# DDS_OUT_channel.net
KiCad netlist of a schematic drawn in Altium Designer
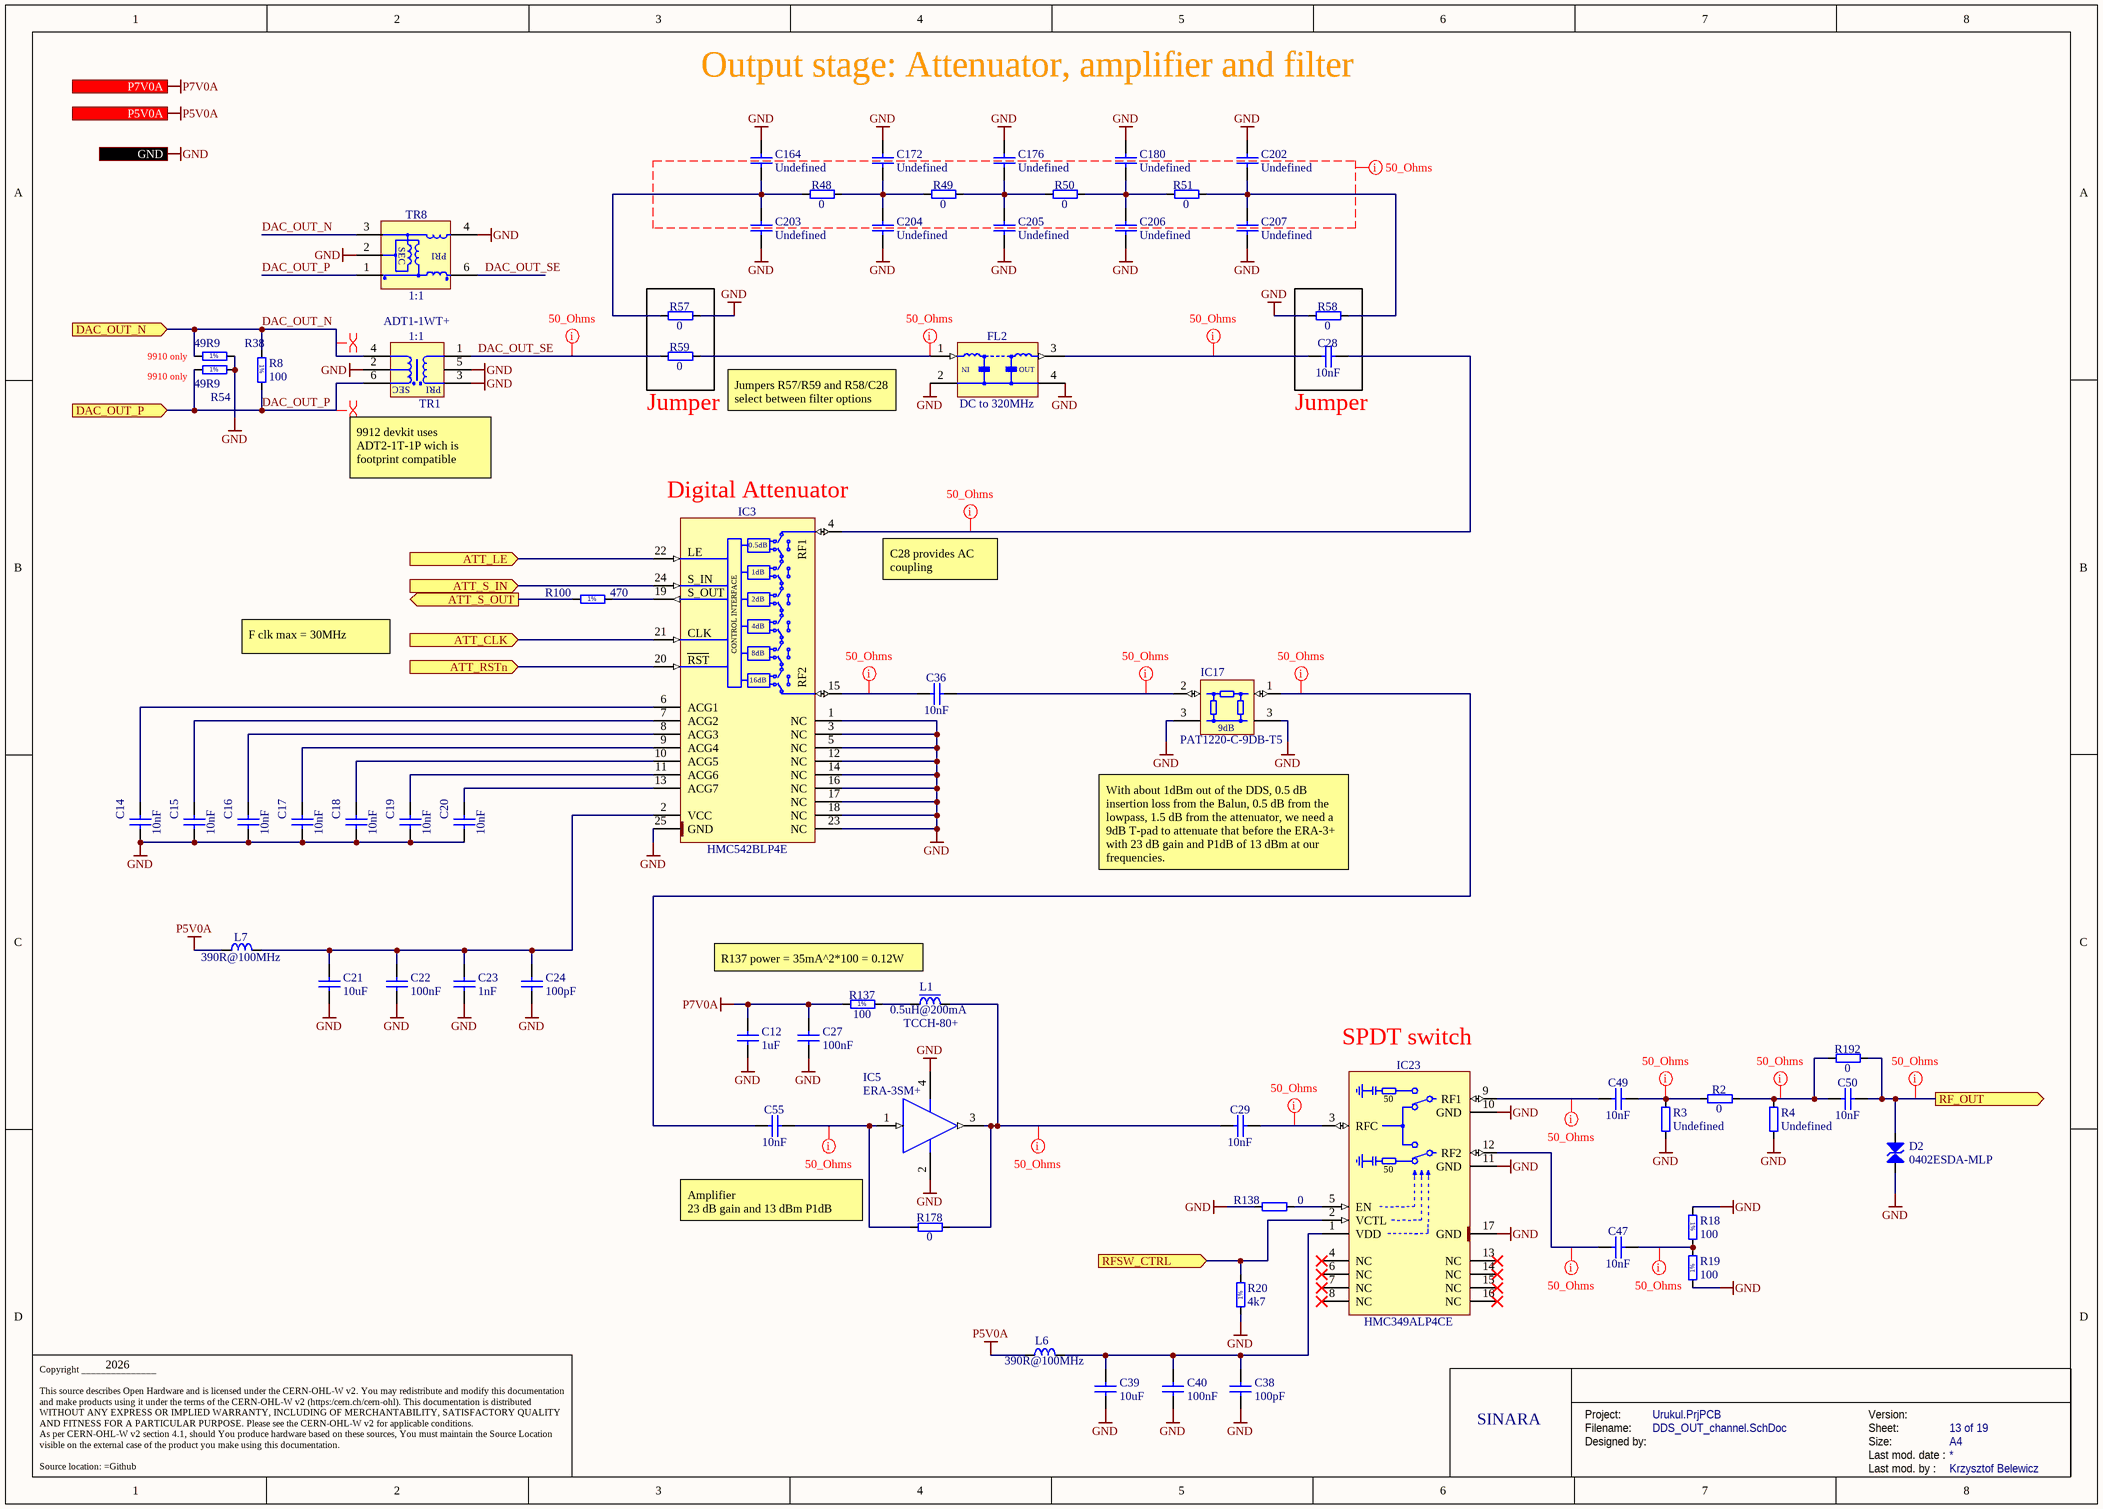
[diagram p0: DDS_OUT_channel.SchDoc]

(export (version "E")
  (design (tool "Eeschema 10.0.6"))
  (components
    (comp (ref "C12")
      (value "1uF")
      (footprint "CAPC2012X140N")
      (description "Non-polarised capacitor")
      (fields
        (field (name "PART NUMBER") "CC0805_1UF_35V_20%_X7R")
        (field (name "VOLTAGE") "35V")
        (field (name "AUTHOR") "CERN DEM JLC")
      )
      (libsource (lib "Capacitors") (part "Capacitor - non polarized"))
    )
    (comp (ref "C14")
      (value "10nF")
      (footprint "CAPC1005X55N")
      (description "Non-polarised capacitor")
      (fields
        (field (name "PART NUMBER") "CC0402_10NF_16V_10%_X7R")
        (field (name "VOLTAGE") "16V")
        (field (name "AUTHOR") "CERN DEM JLC")
      )
      (libsource (lib "Capacitors") (part "Capacitor - non polarized"))
    )
    (comp (ref "C15")
      (value "10nF")
      (footprint "CAPC1005X55N")
      (description "Non-polarised capacitor")
      (fields
        (field (name "PART NUMBER") "CC0402_10NF_16V_10%_X7R")
        (field (name "VOLTAGE") "16V")
        (field (name "AUTHOR") "CERN DEM JLC")
      )
      (libsource (lib "Capacitors") (part "Capacitor - non polarized"))
    )
    (comp (ref "C16")
      (value "10nF")
      (footprint "CAPC1005X55N")
      (description "Non-polarised capacitor")
      (fields
        (field (name "PART NUMBER") "CC0402_10NF_16V_10%_X7R")
        (field (name "VOLTAGE") "16V")
        (field (name "AUTHOR") "CERN DEM JLC")
      )
      (libsource (lib "Capacitors") (part "Capacitor - non polarized"))
    )
    (comp (ref "C17")
      (value "10nF")
      (footprint "CAPC1005X55N")
      (description "Non-polarised capacitor")
      (fields
        (field (name "PART NUMBER") "CC0402_10NF_16V_10%_X7R")
        (field (name "VOLTAGE") "16V")
        (field (name "AUTHOR") "CERN DEM JLC")
      )
      (libsource (lib "Capacitors") (part "Capacitor - non polarized"))
    )
    (comp (ref "C18")
      (value "10nF")
      (footprint "CAPC1005X55N")
      (description "Non-polarised capacitor")
      (fields
        (field (name "PART NUMBER") "CC0402_10NF_16V_10%_X7R")
        (field (name "VOLTAGE") "16V")
        (field (name "AUTHOR") "CERN DEM JLC")
      )
      (libsource (lib "Capacitors") (part "Capacitor - non polarized"))
    )
    (comp (ref "C19")
      (value "10nF")
      (footprint "CAPC1005X55N")
      (description "Non-polarised capacitor")
      (fields
        (field (name "PART NUMBER") "CC0402_10NF_16V_10%_X7R")
        (field (name "VOLTAGE") "16V")
        (field (name "AUTHOR") "CERN DEM JLC")
      )
      (libsource (lib "Capacitors") (part "Capacitor - non polarized"))
    )
    (comp (ref "C20")
      (value "10nF")
      (footprint "CAPC1005X55N")
      (description "Non-polarised capacitor")
      (fields
        (field (name "PART NUMBER") "CC0402_10NF_16V_10%_X7R")
        (field (name "VOLTAGE") "16V")
        (field (name "AUTHOR") "CERN DEM JLC")
      )
      (libsource (lib "Capacitors") (part "Capacitor - non polarized"))
    )
    (comp (ref "C21")
      (value "10uF")
      (footprint "CAPC1608X80N")
      (description "Non-polarised capacitor")
      (fields
        (field (name "PART NUMBER") "CC0603_10UF_16V_20%_X5R")
        (field (name "VOLTAGE") "16V")
        (field (name "AUTHOR") "CERN DEM MR")
      )
      (libsource (lib "Capacitors") (part "Capacitor - non polarized"))
    )
    (comp (ref "C22")
      (value "100nF")
      (footprint "CAPC1005X55N")
      (description "Non-polarised capacitor")
      (fields
        (field (name "PART NUMBER") "CC0402_100NF_16V_10%_X5R")
        (field (name "VOLTAGE") "16V")
        (field (name "AUTHOR") "CERN DEM JLC")
      )
      (libsource (lib "Capacitors") (part "Capacitor - non polarized"))
    )
    (comp (ref "C23")
      (value "1nF")
      (footprint "CAPC1005X55N")
      (description "Non-polarised capacitor")
      (fields
        (field (name "PART NUMBER") "CC0402_1NF_50V_10%_X7R")
        (field (name "VOLTAGE") "50V")
        (field (name "AUTHOR") "CERN DEM JLC")
      )
      (libsource (lib "Capacitors") (part "Capacitor - non polarized"))
    )
    (comp (ref "C24")
      (value "100pF")
      (footprint "CAPC1005X55N")
      (description "Non-polarised capacitor")
      (fields
        (field (name "PART NUMBER") "CC0402_100PF_50V_5%_C0G")
        (field (name "VOLTAGE") "50V")
        (field (name "AUTHOR") "CERN DEM JLC")
      )
      (libsource (lib "Capacitors") (part "Capacitor - non polarized"))
    )
    (comp (ref "C27")
      (value "100nF")
      (footprint "CAPC1005X55N")
      (description "Non-polarised capacitor")
      (fields
        (field (name "PART NUMBER") "CC0402_100NF_16V_10%_X5R")
        (field (name "VOLTAGE") "16V")
        (field (name "AUTHOR") "CERN DEM JLC")
      )
      (libsource (lib "Capacitors") (part "Capacitor - non polarized"))
    )
    (comp (ref "C28")
      (value "10nF")
      (footprint "CAPC1005X55N")
      (description "Non-polarised capacitor")
      (fields
        (field (name "PART NUMBER") "CC0402_10NF_16V_10%_X7R")
        (field (name "VOLTAGE") "16V")
        (field (name "AUTHOR") "CERN DEM JLC")
      )
      (libsource (lib "Capacitors") (part "Capacitor - non polarized"))
    )
    (comp (ref "C29")
      (value "10nF")
      (footprint "CAPC1005X55N")
      (description "Non-polarised capacitor")
      (fields
        (field (name "PART NUMBER") "CC0402_10NF_16V_10%_X7R")
        (field (name "VOLTAGE") "16V")
        (field (name "AUTHOR") "CERN DEM JLC")
      )
      (libsource (lib "Capacitors") (part "Capacitor - non polarized"))
    )
    (comp (ref "C36")
      (value "10nF")
      (footprint "CAPC1005X55N")
      (description "Non-polarised capacitor")
      (fields
        (field (name "PART NUMBER") "CC0402_10NF_16V_10%_X7R")
        (field (name "VOLTAGE") "16V")
        (field (name "AUTHOR") "CERN DEM JLC")
      )
      (libsource (lib "Capacitors") (part "Capacitor - non polarized"))
    )
    (comp (ref "C38")
      (value "100pF")
      (footprint "CAPC1005X55N")
      (description "Non-polarised capacitor")
      (fields
        (field (name "PART NUMBER") "CC0402_100PF_50V_5%_C0G")
        (field (name "VOLTAGE") "50V")
        (field (name "AUTHOR") "CERN DEM JLC")
      )
      (libsource (lib "Capacitors") (part "Capacitor - non polarized"))
    )
    (comp (ref "C39")
      (value "10uF")
      (footprint "CAPC1608X80N")
      (description "Non-polarised capacitor")
      (fields
        (field (name "PART NUMBER") "CC0603_10UF_16V_20%_X5R")
        (field (name "VOLTAGE") "16V")
        (field (name "AUTHOR") "CERN DEM MR")
      )
      (libsource (lib "Capacitors") (part "Capacitor - non polarized"))
    )
    (comp (ref "C40")
      (value "100nF")
      (footprint "CAPC1005X55N")
      (description "Non-polarised capacitor")
      (fields
        (field (name "PART NUMBER") "CC0402_100NF_16V_10%_X5R")
        (field (name "VOLTAGE") "16V")
        (field (name "AUTHOR") "CERN DEM JLC")
      )
      (libsource (lib "Capacitors") (part "Capacitor - non polarized"))
    )
    (comp (ref "C47")
      (value "10nF")
      (footprint "CAPC1005X55N")
      (description "Non-polarised capacitor")
      (fields
        (field (name "PART NUMBER") "CC0402_10NF_16V_10%_X7R")
        (field (name "VOLTAGE") "16V")
        (field (name "AUTHOR") "CERN DEM JLC")
      )
      (libsource (lib "Capacitors") (part "Capacitor - non polarized"))
    )
    (comp (ref "C49")
      (value "10nF")
      (footprint "CAPC1005X55N")
      (description "Non-polarised capacitor")
      (fields
        (field (name "PART NUMBER") "CC0402_10NF_16V_10%_X7R")
        (field (name "VOLTAGE") "16V")
        (field (name "AUTHOR") "CERN DEM JLC")
      )
      (libsource (lib "Capacitors") (part "Capacitor - non polarized"))
    )
    (comp (ref "C50")
      (value "10nF")
      (footprint "CAPC1005X55N")
      (description "Non-polarised capacitor")
      (fields
        (field (name "PART NUMBER") "CC0402_10NF_16V_10%_X7R")
        (field (name "VOLTAGE") "16V")
        (field (name "AUTHOR") "CERN DEM JLC")
      )
      (libsource (lib "Capacitors") (part "Capacitor - non polarized"))
    )
    (comp (ref "C55")
      (value "10nF")
      (footprint "CAPC1005X55N")
      (description "Non-polarised capacitor")
      (fields
        (field (name "PART NUMBER") "CC0402_10NF_16V_10%_X7R")
        (field (name "VOLTAGE") "16V")
        (field (name "AUTHOR") "CERN DEM JLC")
      )
      (libsource (lib "Capacitors") (part "Capacitor - non polarized"))
    )
    (comp (ref "C164")
      (value "Undefined")
      (footprint "CAPC1005X55N")
      (description "Non-polarised capacitor")
      (fields (field (name "PART NUMBER") "CC0402_NO-VALUE") (field (name "AUTHOR") "CERN DEM JLC"))
      (libsource (lib "Capacitors") (part "Capacitor - non polarized"))
    )
    (comp (ref "C172")
      (value "Undefined")
      (footprint "CAPC1005X55N")
      (description "Non-polarised capacitor")
      (fields (field (name "PART NUMBER") "CC0402_NO-VALUE") (field (name "AUTHOR") "CERN DEM JLC"))
      (libsource (lib "Capacitors") (part "Capacitor - non polarized"))
    )
    (comp (ref "C176")
      (value "Undefined")
      (footprint "CAPC1005X55N")
      (description "Non-polarised capacitor")
      (fields (field (name "PART NUMBER") "CC0402_NO-VALUE") (field (name "AUTHOR") "CERN DEM JLC"))
      (libsource (lib "Capacitors") (part "Capacitor - non polarized"))
    )
    (comp (ref "C180")
      (value "Undefined")
      (footprint "CAPC1005X55N")
      (description "Non-polarised capacitor")
      (fields (field (name "PART NUMBER") "CC0402_NO-VALUE") (field (name "AUTHOR") "CERN DEM JLC"))
      (libsource (lib "Capacitors") (part "Capacitor - non polarized"))
    )
    (comp (ref "C202")
      (value "Undefined")
      (footprint "CAPC1005X55N")
      (description "Non-polarised capacitor")
      (fields (field (name "PART NUMBER") "CC0402_NO-VALUE") (field (name "AUTHOR") "CERN DEM JLC"))
      (libsource (lib "Capacitors") (part "Capacitor - non polarized"))
    )
    (comp (ref "C203")
      (value "Undefined")
      (footprint "CAPC1005X55N")
      (description "Non-polarised capacitor")
      (fields (field (name "PART NUMBER") "CC0402_NO-VALUE") (field (name "AUTHOR") "CERN DEM JLC"))
      (libsource (lib "Capacitors") (part "Capacitor - non polarized"))
    )
    (comp (ref "C204")
      (value "Undefined")
      (footprint "CAPC1005X55N")
      (description "Non-polarised capacitor")
      (fields (field (name "PART NUMBER") "CC0402_NO-VALUE") (field (name "AUTHOR") "CERN DEM JLC"))
      (libsource (lib "Capacitors") (part "Capacitor - non polarized"))
    )
    (comp (ref "C205")
      (value "Undefined")
      (footprint "CAPC1005X55N")
      (description "Non-polarised capacitor")
      (fields (field (name "PART NUMBER") "CC0402_NO-VALUE") (field (name "AUTHOR") "CERN DEM JLC"))
      (libsource (lib "Capacitors") (part "Capacitor - non polarized"))
    )
    (comp (ref "C206")
      (value "Undefined")
      (footprint "CAPC1005X55N")
      (description "Non-polarised capacitor")
      (fields (field (name "PART NUMBER") "CC0402_NO-VALUE") (field (name "AUTHOR") "CERN DEM JLC"))
      (libsource (lib "Capacitors") (part "Capacitor - non polarized"))
    )
    (comp (ref "C207")
      (value "Undefined")
      (footprint "CAPC1005X55N")
      (description "Non-polarised capacitor")
      (fields (field (name "PART NUMBER") "CC0402_NO-VALUE") (field (name "AUTHOR") "CERN DEM JLC"))
      (libsource (lib "Capacitors") (part "Capacitor - non polarized"))
    )
    (comp (ref "D2")
      (value "0402ESDA-MLP")
      (footprint "EATON_0402ESDA-MLP")
      (description "Transient Voltage Suppressor Diode (Bi-Directional)")
      (fields
        (field (name "VOLTAGE") "8kV")
        (field (name "MANUFACTURER") "EATON")
        (field (name "AUTHOR") "CERN DEM MR")
      )
      (libsource (lib "ICs And Semiconductors") (part "Diode TVS Bi-Directional"))
    )
    (comp (ref "FL2")
      (value "DC to 320MHz")
      (footprint "FIL_MINI-CIRCUITS_FV1206")
      (description "50 Ohm DC to 320MHz Low Pass Filter")
      (fields
        (field (name "PART NUMBER") "FIL_MINI-CIRCUITS_LFCN-320")
        (field (name "MANUFACTURER") "MINI-CIRCUITS")
        (field (name "AUTHOR") "CERN DEM JLC")
      )
      (libsource (lib "LIBRARY_SCH") (part "FIL_MINI-CIRCUITS_LFCN-320"))
    )
    (comp (ref "IC3")
      (value "HMC542BLP4E")
      (footprint "QFN50P400X400X100-25N-S295")
      (description "0.5dB LSB GaAs MMIC 6-bit Digital Serial Control Attenuator, DC - 4GHz")
      (fields (field (name "MANUFACTURER") "HITTITE MICROWAVE CORP") (field (name "AUTHOR") "CERN DEM JMW"))
      (libsource (lib "ICs And Semiconductors") (part "HMC542BLP4E"))
    )
    (comp (ref "IC5")
      (value "ERA-3SM+")
      (footprint "MINI-CIRCUITS_WW107")
      (description "DC-3GHz Monolithic Amplifier")
      (fields (field (name "MANUFACTURER") "MINI-CIRCUITS") (field (name "AUTHOR") "GK"))
      (libsource (lib "LIBRARY_SCH") (part "RF_ERA-3SM+"))
    )
    (comp (ref "IC17")
      (value "PAT1220-C-9DB-T5")
      (footprint "SUSUMU_PAT1220")
      (description "DC to 10GHz, 100mw, 50 Ohm, 9dB, Precision chip attenuator")
      (fields (field (name "MANUFACTURER") "SUSUMU") (field (name "AUTHOR") "GK"))
      (libsource (lib "LIBRARY_SCH") (part "RF_PAT1220-C-9DB-T5"))
    )
    (comp (ref "IC23")
      (value "HMC349ALP4CE")
      (footprint "QFN65P400X400X100-17N-S255")
      (description "DC-4GHz High Isolation SPDT Non-Reflective Switch")
      (fields (field (name "MANUFACTURER") "ANALOG DEVICES") (field (name "AUTHOR") "CERN DEM JLC"))
      (libsource (lib "ICs And Semiconductors") (part "HMC349ALP4CE"))
    )
    (comp (ref "L1")
      (value "0.5uH@200mA")
      (footprint "IND_MINI-CIRCUITS_GU1604")
      (description "50 Ohms, 50 to 8200 MHz RF Choke")
      (fields
        (field (name "PART NUMBER") "IND_MINI-CIRCUITS_TCCH-80+")
        (field (name "POWER") "200mA")
        (field (name "MANUFACTURER PART NUMBER") "TCCH-80+")
        (field (name "AUTHOR") "CERN DEM JLC")
      )
      (libsource (lib "Inductors & Transformers") (part "IND_MINI-CIRCUITS_TCCH-80+"))
    )
    (comp (ref "L6")
      (value "390R@100MHz")
      (footprint "INDC1608X95N")
      (description "Inductor")
      (fields
        (field (name "PART NUMBER") "IND0603_TDK_MPZ1608R391A")
        (field (name "POWER") "1.2A")
        (field (name "AUTHOR") "CERN DEM JLC")
      )
      (libsource (lib "Inductors & Transformers") (part "Inductor"))
    )
    (comp (ref "L7")
      (value "390R@100MHz")
      (footprint "INDC1608X95N")
      (description "Inductor")
      (fields
        (field (name "PART NUMBER") "IND0603_TDK_MPZ1608R391A")
        (field (name "POWER") "1.2A")
        (field (name "AUTHOR") "CERN DEM JLC")
      )
      (libsource (lib "") (part "Inductor_1"))
    )
    (comp (ref "R2")
      (value "0")
      (footprint "RESC1005X40N")
      (description "Resistor")
      (fields
        (field (name "PART NUMBER") "R0402_0R_JUMPER")
        (field (name "MANUFACTURER") "GENERIC")
        (field (name "AUTHOR") "CERN DEM JLC")
      )
      (libsource (lib "Resistors") (part "Resistor"))
    )
    (comp (ref "R3")
      (value "Undefined")
      (footprint "RESC1005X40N")
      (description "Resistor")
      (fields (field (name "PART NUMBER") "R0402_NO-VALUE") (field (name "AUTHOR") "CERN DEM JLC"))
      (libsource (lib "Resistors") (part "Resistor"))
    )
    (comp (ref "R4")
      (value "Undefined")
      (footprint "RESC1005X40N")
      (description "Resistor")
      (fields (field (name "PART NUMBER") "R0402_NO-VALUE") (field (name "AUTHOR") "CERN DEM JLC"))
      (libsource (lib "Resistors") (part "Resistor"))
    )
    (comp (ref "R8")
      (value "100")
      (footprint "RESC1005X40N")
      (description "Resistor - 1%")
      (fields
        (field (name "PART NUMBER") "R0402_100R_1%_0.0625W_100PPM")
        (field (name "POWER") "0.0625W")
        (field (name "AUTHOR") "CERN DEM JLC")
      )
      (libsource (lib "Resistors") (part "Resistor - 1%"))
    )
    (comp (ref "R18")
      (value "100")
      (footprint "RESC1005X40N")
      (description "Resistor - 1%")
      (fields
        (field (name "PART NUMBER") "R0402_100R_1%_0.0625W_100PPM")
        (field (name "POWER") "0.0625W")
        (field (name "AUTHOR") "CERN DEM JLC")
      )
      (libsource (lib "Resistors") (part "Resistor - 1%"))
    )
    (comp (ref "R19")
      (value "100")
      (footprint "RESC1005X40N")
      (description "Resistor - 1%")
      (fields
        (field (name "PART NUMBER") "R0402_100R_1%_0.0625W_100PPM")
        (field (name "POWER") "0.0625W")
        (field (name "AUTHOR") "CERN DEM JLC")
      )
      (libsource (lib "Resistors") (part "Resistor - 1%"))
    )
    (comp (ref "R20")
      (value "4k7")
      (footprint "RESC1005X40N")
      (description "Resistor - 1%")
      (fields
        (field (name "PART NUMBER") "R0402_4K7_1%_0.0625W_100PPM")
        (field (name "POWER") "0.0625W")
        (field (name "AUTHOR") "CERN DEM JLC")
      )
      (libsource (lib "Resistors") (part "Resistor - 1%"))
    )
    (comp (ref "R38")
      (value "49R9")
      (footprint "RESC1005X40N")
      (description "Resistor - 1%")
      (fields
        (field (name "PART NUMBER") "R0402_49R9_1%_0.0625W_100PPM")
        (field (name "POWER") "0.0625W")
        (field (name "AUTHOR") "CERN DEM JLC")
      )
      (libsource (lib "Resistors") (part "Resistor - 1%"))
    )
    (comp (ref "R48")
      (value "0")
      (footprint "RESC1005X40N")
      (description "Resistor")
      (fields
        (field (name "PART NUMBER") "R0402_0R_JUMPER")
        (field (name "MANUFACTURER") "GENERIC")
        (field (name "AUTHOR") "CERN DEM JLC")
      )
      (libsource (lib "Resistors") (part "Resistor"))
    )
    (comp (ref "R49")
      (value "0")
      (footprint "RESC1005X40N")
      (description "Resistor")
      (fields
        (field (name "PART NUMBER") "R0402_0R_JUMPER")
        (field (name "MANUFACTURER") "GENERIC")
        (field (name "AUTHOR") "CERN DEM JLC")
      )
      (libsource (lib "Resistors") (part "Resistor"))
    )
    (comp (ref "R50")
      (value "0")
      (footprint "RESC1005X40N")
      (description "Resistor")
      (fields
        (field (name "PART NUMBER") "R0402_0R_JUMPER")
        (field (name "MANUFACTURER") "GENERIC")
        (field (name "AUTHOR") "CERN DEM JLC")
      )
      (libsource (lib "Resistors") (part "Resistor"))
    )
    (comp (ref "R51")
      (value "0")
      (footprint "RESC1005X40N")
      (description "Resistor")
      (fields
        (field (name "PART NUMBER") "R0402_0R_JUMPER")
        (field (name "MANUFACTURER") "GENERIC")
        (field (name "AUTHOR") "CERN DEM JLC")
      )
      (libsource (lib "Resistors") (part "Resistor"))
    )
    (comp (ref "R54")
      (value "49R9")
      (footprint "RESC1005X40N")
      (description "Resistor - 1%")
      (fields
        (field (name "PART NUMBER") "R0402_49R9_1%_0.0625W_100PPM")
        (field (name "POWER") "0.0625W")
        (field (name "AUTHOR") "CERN DEM JLC")
      )
      (libsource (lib "Resistors") (part "Resistor - 1%"))
    )
    (comp (ref "R57")
      (value "0")
      (footprint "RESC1005X40N")
      (description "Resistor")
      (fields
        (field (name "PART NUMBER") "R0402_0R_JUMPER")
        (field (name "MANUFACTURER") "GENERIC")
        (field (name "AUTHOR") "CERN DEM JLC")
      )
      (libsource (lib "Resistors") (part "Resistor"))
    )
    (comp (ref "R58")
      (value "0")
      (footprint "RESC1005X40N")
      (description "Resistor")
      (fields
        (field (name "PART NUMBER") "R0402_0R_JUMPER")
        (field (name "MANUFACTURER") "GENERIC")
        (field (name "AUTHOR") "CERN DEM JLC")
      )
      (libsource (lib "Resistors") (part "Resistor"))
    )
    (comp (ref "R59")
      (value "0")
      (footprint "RESC1005X40N")
      (description "Resistor")
      (fields
        (field (name "PART NUMBER") "R0402_0R_JUMPER")
        (field (name "MANUFACTURER") "GENERIC")
        (field (name "AUTHOR") "CERN DEM JLC")
      )
      (libsource (lib "Resistors") (part "Resistor"))
    )
    (comp (ref "R100")
      (value "470")
      (footprint "RESC1005X40N")
      (description "Resistor - 1%")
      (fields
        (field (name "PART NUMBER") "R0402_470R_1%_0.0625W_100PPM")
        (field (name "POWER") "0.0625W")
        (field (name "AUTHOR") "CERN DEM JLC")
      )
      (libsource (lib "Resistors") (part "Resistor - 1%"))
    )
    (comp (ref "R137")
      (value "100")
      (footprint "RESC3216X65N")
      (description "Resistor - 1%")
      (fields
        (field (name "PART NUMBER") "R1206_100R_1%_0.5W_100PPM_VISHAY_CRCW-HP e3")
        (field (name "POWER") "0.5W")
        (field (name "AUTHOR") "CERN DEM JLC")
      )
      (libsource (lib "Resistors") (part "Resistor - 1%"))
    )
    (comp (ref "R138")
      (value "0")
      (footprint "RESC1005X40N")
      (description "Resistor")
      (fields
        (field (name "PART NUMBER") "R0402_0R_JUMPER")
        (field (name "MANUFACTURER") "GENERIC")
        (field (name "AUTHOR") "CERN DEM JLC")
      )
      (libsource (lib "Resistors") (part "Resistor"))
    )
    (comp (ref "R178")
      (value "0")
      (footprint "RESC1608X55N")
      (description "Resistor")
      (fields
        (field (name "PART NUMBER") "R0603_0R_JUMPER")
        (field (name "MANUFACTURER") "GENERIC")
        (field (name "AUTHOR") "CERN DEM JLC")
      )
      (libsource (lib "Resistors") (part "Resistor"))
    )
    (comp (ref "R192")
      (value "0")
      (footprint "RESC1005X40N")
      (description "Resistor")
      (fields
        (field (name "PART NUMBER") "R0402_0R_JUMPER")
        (field (name "MANUFACTURER") "GENERIC")
        (field (name "AUTHOR") "CERN DEM JLC")
      )
      (libsource (lib "Resistors") (part "Resistor"))
    )
    (comp (ref "TR1")
      (value "1:1")
      (footprint "XFMR_MINI-CIRCUITS_CD542")
      (description "75 Ohm 0.4 To 800MHz RF Transformers")
      (fields
        (field (name "PART NUMBER") "XFMR_MINI-CIRCUITS_ADT1-1WT+")
        (field (name "MANUFACTURER") "MINI-CIRCUITS")
        (field (name "MANUFACTURER PART NUMBER") "ADT1-1WT+")
        (field (name "AUTHOR") "CERN DEM JLC")
      )
      (libsource (lib "Inductors & Transformers") (part "XFMR_MINI-CIRCUITS_ADT1-1WT+"))
    )
    (comp (ref "TR8")
      (value "1:1")
      (footprint "XFMR_MINI-CIRCUITS_AT1521")
      (description "50 Ohms 5 To 1500MHz TLT RF Transformer")
      (fields
        (field (name "PART NUMBER") "XFMR_MINI-CIRCUITS_TC1-1T-152X+")
        (field (name "MANUFACTURER") "MINI-CIRCUITS")
        (field (name "AUTHOR") "GK")
      )
      (libsource (lib "Inductors_Transformers") (part "XFMR_MINI-CIRCUITS_TC1-1T-152X+"))
    )
  )
  (nets
    (net (code "1") (name "/ATT_CLK") (class "Default")
      (node (ref "IC3") (pin "21") (pinfunction "SHIFT_CLOCK_21") (pintype "input"))
    )
    (net (code "2") (name "/ATT_LE") (class "Default")
      (node (ref "IC3") (pin "22") (pinfunction "LATCH_ENABLE_22") (pintype "input"))
    )
    (net (code "3") (name "/ATT_RSTn") (class "Default")
      (node (ref "IC3") (pin "20") (pinfunction "~{RESET}_20") (pintype "input"))
    )
    (net (code "4") (name "/ATT_S_IN") (class "Default")
      (node (ref "IC3") (pin "24") (pinfunction "SERIAL_INPUT_24") (pintype "input"))
    )
    (net (code "5") (name "/ATT_S_OUT") (class "Default")
      (node (ref "R100") (pin "1") (pinfunction "1_1") (pintype "passive"))
    )
    (net (code "6") (name "/DAC_OUT_N") (class "Default")
      (node (ref "R38") (pin "1") (pinfunction "1_1") (pintype "passive"))
      (node (ref "R8") (pin "1") (pinfunction "1_1") (pintype "passive"))
      (node (ref "TR1") (pin "4") (pinfunction "S_4") (pintype "passive"))
      (node (ref "TR8") (pin "3") (pinfunction "S_3") (pintype "passive"))
    )
    (net (code "7") (name "/DAC_OUT_P") (class "Default")
      (node (ref "R54") (pin "1") (pinfunction "1_1") (pintype "passive"))
      (node (ref "R8") (pin "2") (pinfunction "2_2") (pintype "passive"))
      (node (ref "TR1") (pin "6") (pinfunction "SDOT_6") (pintype "passive"))
      (node (ref "TR8") (pin "1") (pinfunction "SDOT_1") (pintype "passive"))
    )
    (net (code "8") (name "/DAC_OUT_SE") (class "Default")
      (node (ref "R59") (pin "1") (pinfunction "1_1") (pintype "passive"))
      (node (ref "TR1") (pin "1") (pinfunction "P_1") (pintype "passive"))
      (node (ref "TR8") (pin "6") (pinfunction "PDOT_6") (pintype "passive"))
    )
    (net (code "9") (name "/RFSW_CTRL") (class "Default")
      (node (ref "IC23") (pin "2") (pinfunction "VCTL_2") (pintype "input"))
      (node (ref "R20") (pin "2") (pinfunction "2_2") (pintype "passive"))
    )
    (net (code "10") (name "/RF_OUT") (class "Default")
      (node (ref "C50") (pin "2") (pinfunction "2_2") (pintype "passive"))
      (node (ref "D2") (pin "2") (pinfunction "2_2") (pintype "passive"))
      (node (ref "R192") (pin "2") (pinfunction "2_2") (pintype "passive"))
    )
    (net (code "11") (name "GND") (class "Default")
      (node (ref "C12") (pin "1") (pinfunction "1_1") (pintype "passive"))
      (node (ref "C14") (pin "1") (pinfunction "1_1") (pintype "passive"))
      (node (ref "C15") (pin "1") (pinfunction "1_1") (pintype "passive"))
      (node (ref "C16") (pin "1") (pinfunction "1_1") (pintype "passive"))
      (node (ref "C164") (pin "2") (pinfunction "2_2") (pintype "passive"))
      (node (ref "C17") (pin "1") (pinfunction "1_1") (pintype "passive"))
      (node (ref "C172") (pin "2") (pinfunction "2_2") (pintype "passive"))
      (node (ref "C176") (pin "2") (pinfunction "2_2") (pintype "passive"))
      (node (ref "C18") (pin "1") (pinfunction "1_1") (pintype "passive"))
      (node (ref "C180") (pin "2") (pinfunction "2_2") (pintype "passive"))
      (node (ref "C19") (pin "1") (pinfunction "1_1") (pintype "passive"))
      (node (ref "C20") (pin "1") (pinfunction "1_1") (pintype "passive"))
      (node (ref "C202") (pin "2") (pinfunction "2_2") (pintype "passive"))
      (node (ref "C203") (pin "1") (pinfunction "1_1") (pintype "passive"))
      (node (ref "C204") (pin "1") (pinfunction "1_1") (pintype "passive"))
      (node (ref "C205") (pin "1") (pinfunction "1_1") (pintype "passive"))
      (node (ref "C206") (pin "1") (pinfunction "1_1") (pintype "passive"))
      (node (ref "C207") (pin "1") (pinfunction "1_1") (pintype "passive"))
      (node (ref "C21") (pin "1") (pinfunction "1_1") (pintype "passive"))
      (node (ref "C22") (pin "1") (pinfunction "1_1") (pintype "passive"))
      (node (ref "C23") (pin "1") (pinfunction "1_1") (pintype "passive"))
      (node (ref "C24") (pin "1") (pinfunction "1_1") (pintype "passive"))
      (node (ref "C27") (pin "1") (pinfunction "1_1") (pintype "passive"))
      (node (ref "C38") (pin "2") (pinfunction "2_2") (pintype "passive"))
      (node (ref "C39") (pin "1") (pinfunction "1_1") (pintype "passive"))
      (node (ref "C40") (pin "1") (pinfunction "1_1") (pintype "passive"))
      (node (ref "D2") (pin "1") (pinfunction "1_1") (pintype "passive"))
      (node (ref "FL2") (pin "2") (pinfunction "GND_2") (pintype "power_in"))
      (node (ref "FL2") (pin "4") (pinfunction "GND_4") (pintype "power_in"))
      (node (ref "IC17") (pin "3") (pinfunction "GND_3") (pintype "passive"))
      (node (ref "IC23") (pin "10") (pinfunction "GND_10") (pintype "power_in"))
      (node (ref "IC23") (pin "11") (pinfunction "GND_11") (pintype "power_in"))
      (node (ref "IC23") (pin "17") (pinfunction "GND_17") (pintype "power_in"))
      (node (ref "IC3") (pin "1") (pinfunction "NC_1") (pintype "passive"))
      (node (ref "IC3") (pin "12") (pinfunction "NC_12") (pintype "passive"))
      (node (ref "IC3") (pin "14") (pinfunction "NC_14") (pintype "passive"))
      (node (ref "IC3") (pin "16") (pinfunction "NC_16") (pintype "passive"))
      (node (ref "IC3") (pin "17") (pinfunction "NC_17") (pintype "passive"))
      (node (ref "IC3") (pin "18") (pinfunction "NC_18") (pintype "passive"))
      (node (ref "IC3") (pin "23") (pinfunction "NC_23") (pintype "passive"))
      (node (ref "IC3") (pin "25") (pinfunction "GND_25") (pintype "power_in"))
      (node (ref "IC3") (pin "3") (pinfunction "NC_3") (pintype "passive"))
      (node (ref "IC3") (pin "5") (pinfunction "NC_5") (pintype "passive"))
      (node (ref "IC5") (pin "2") (pinfunction "GND_2") (pintype "power_in"))
      (node (ref "IC5") (pin "4") (pinfunction "GND_4") (pintype "power_in"))
      (node (ref "R138") (pin "1") (pinfunction "1_1") (pintype "passive"))
      (node (ref "R18") (pin "1") (pinfunction "1_1") (pintype "passive"))
      (node (ref "R19") (pin "1") (pinfunction "1_1") (pintype "passive"))
      (node (ref "R20") (pin "1") (pinfunction "1_1") (pintype "passive"))
      (node (ref "R3") (pin "1") (pinfunction "1_1") (pintype "passive"))
      (node (ref "R38") (pin "2") (pinfunction "2_2") (pintype "passive"))
      (node (ref "R4") (pin "1") (pinfunction "1_1") (pintype "passive"))
      (node (ref "R54") (pin "2") (pinfunction "2_2") (pintype "passive"))
      (node (ref "R57") (pin "2") (pinfunction "2_2") (pintype "passive"))
      (node (ref "R58") (pin "2") (pinfunction "2_2") (pintype "passive"))
      (node (ref "TR1") (pin "2") (pinfunction "SCT_2") (pintype "passive"))
      (node (ref "TR1") (pin "3") (pinfunction "PDOT_3") (pintype "passive"))
      (node (ref "TR1") (pin "5") (pinfunction "NC_5") (pintype "passive"))
      (node (ref "TR8") (pin "2") (pinfunction "SCT_2") (pintype "passive"))
      (node (ref "TR8") (pin "4") (pinfunction "P_4") (pintype "passive"))
    )
    (net (code "12") (name "Net-(C47-Pad2)") (class "Default")
      (node (ref "C47") (pin "2") (pinfunction "2_2") (pintype "passive"))
      (node (ref "R18") (pin "2") (pinfunction "2_2") (pintype "passive"))
      (node (ref "R19") (pin "2") (pinfunction "2_2") (pintype "passive"))
    )
    (net (code "13") (name "Net-(C49-Pad2)") (class "Default")
      (node (ref "C49") (pin "2") (pinfunction "2_2") (pintype "passive"))
      (node (ref "R2") (pin "1") (pinfunction "1_1") (pintype "passive"))
      (node (ref "R3") (pin "2") (pinfunction "2_2") (pintype "passive"))
    )
    (net (code "14") (name "Net-(C50-Pad1)") (class "Default")
      (node (ref "C50") (pin "1") (pinfunction "1_1") (pintype "passive"))
      (node (ref "R192") (pin "1") (pinfunction "1_1") (pintype "passive"))
      (node (ref "R2") (pin "2") (pinfunction "2_2") (pintype "passive"))
      (node (ref "R4") (pin "2") (pinfunction "2_2") (pintype "passive"))
    )
    (net (code "15") (name "Net-(C164-Pad1)") (class "Default")
      (node (ref "C164") (pin "1") (pinfunction "1_1") (pintype "passive"))
      (node (ref "C203") (pin "2") (pinfunction "2_2") (pintype "passive"))
      (node (ref "R48") (pin "1") (pinfunction "1_1") (pintype "passive"))
      (node (ref "R57") (pin "1") (pinfunction "1_1") (pintype "passive"))
    )
    (net (code "16") (name "Net-(C172-Pad1)") (class "Default")
      (node (ref "C172") (pin "1") (pinfunction "1_1") (pintype "passive"))
      (node (ref "C204") (pin "2") (pinfunction "2_2") (pintype "passive"))
      (node (ref "R48") (pin "2") (pinfunction "2_2") (pintype "passive"))
      (node (ref "R49") (pin "1") (pinfunction "1_1") (pintype "passive"))
    )
    (net (code "17") (name "Net-(C176-Pad1)") (class "Default")
      (node (ref "C176") (pin "1") (pinfunction "1_1") (pintype "passive"))
      (node (ref "C205") (pin "2") (pinfunction "2_2") (pintype "passive"))
      (node (ref "R49") (pin "2") (pinfunction "2_2") (pintype "passive"))
      (node (ref "R50") (pin "1") (pinfunction "1_1") (pintype "passive"))
    )
    (net (code "18") (name "Net-(C180-Pad1)") (class "Default")
      (node (ref "C180") (pin "1") (pinfunction "1_1") (pintype "passive"))
      (node (ref "C206") (pin "2") (pinfunction "2_2") (pintype "passive"))
      (node (ref "R50") (pin "2") (pinfunction "2_2") (pintype "passive"))
      (node (ref "R51") (pin "2") (pinfunction "2_2") (pintype "passive"))
    )
    (net (code "19") (name "Net-(C202-Pad1)") (class "Default")
      (node (ref "C202") (pin "1") (pinfunction "1_1") (pintype "passive"))
      (node (ref "C207") (pin "2") (pinfunction "2_2") (pintype "passive"))
      (node (ref "R51") (pin "1") (pinfunction "1_1") (pintype "passive"))
      (node (ref "R58") (pin "1") (pinfunction "1_1") (pintype "passive"))
    )
    (net (code "20") (name "Net-(FL2-RFIN)") (class "Default")
      (node (ref "FL2") (pin "1") (pinfunction "RFIN_1") (pintype "input"))
      (node (ref "R59") (pin "2") (pinfunction "2_2") (pintype "passive"))
    )
    (net (code "21") (name "Net-(FL2-RFOUT)") (class "Default")
      (node (ref "C28") (pin "1") (pinfunction "1_1") (pintype "passive"))
      (node (ref "FL2") (pin "3") (pinfunction "RFOUT_3") (pintype "output"))
    )
    (net (code "22") (name "Net-(IC3-ACG1)") (class "Default")
      (node (ref "C14") (pin "2") (pinfunction "2_2") (pintype "passive"))
      (node (ref "IC3") (pin "6") (pinfunction "ACG1_6") (pintype "passive"))
    )
    (net (code "23") (name "Net-(IC3-ACG2)") (class "Default")
      (node (ref "C15") (pin "2") (pinfunction "2_2") (pintype "passive"))
      (node (ref "IC3") (pin "7") (pinfunction "ACG2_7") (pintype "passive"))
    )
    (net (code "24") (name "Net-(IC3-ACG3)") (class "Default")
      (node (ref "C16") (pin "2") (pinfunction "2_2") (pintype "passive"))
      (node (ref "IC3") (pin "8") (pinfunction "ACG3_8") (pintype "passive"))
    )
    (net (code "25") (name "Net-(IC3-ACG4)") (class "Default")
      (node (ref "C17") (pin "2") (pinfunction "2_2") (pintype "passive"))
      (node (ref "IC3") (pin "9") (pinfunction "ACG4_9") (pintype "passive"))
    )
    (net (code "26") (name "Net-(IC3-ACG5)") (class "Default")
      (node (ref "C18") (pin "2") (pinfunction "2_2") (pintype "passive"))
      (node (ref "IC3") (pin "10") (pinfunction "ACG5_10") (pintype "passive"))
    )
    (net (code "27") (name "Net-(IC3-ACG6)") (class "Default")
      (node (ref "C19") (pin "2") (pinfunction "2_2") (pintype "passive"))
      (node (ref "IC3") (pin "11") (pinfunction "ACG6_11") (pintype "passive"))
    )
    (net (code "28") (name "Net-(IC3-ACG7)") (class "Default")
      (node (ref "C20") (pin "2") (pinfunction "2_2") (pintype "passive"))
      (node (ref "IC3") (pin "13") (pinfunction "ACG7_13") (pintype "passive"))
    )
    (net (code "29") (name "Net-(IC3-RF1)") (class "Default")
      (node (ref "C28") (pin "2") (pinfunction "2_2") (pintype "passive"))
      (node (ref "IC3") (pin "4") (pinfunction "RF1_4") (pintype "bidirectional"))
    )
    (net (code "30") (name "Net-(IC3-RF2)") (class "Default")
      (node (ref "C36") (pin "1") (pinfunction "1_1") (pintype "passive"))
      (node (ref "IC3") (pin "15") (pinfunction "RF2_15") (pintype "bidirectional"))
    )
    (net (code "31") (name "Net-(IC3-SERIAL_OUTPUT)") (class "Default")
      (node (ref "IC3") (pin "19") (pinfunction "SERIAL_OUTPUT_19") (pintype "output"))
      (node (ref "R100") (pin "2") (pinfunction "2_2") (pintype "passive"))
    )
    (net (code "32") (name "Net-(IC3-VCC)") (class "Default")
      (node (ref "C21") (pin "2") (pinfunction "2_2") (pintype "passive"))
      (node (ref "C22") (pin "2") (pinfunction "2_2") (pintype "passive"))
      (node (ref "C23") (pin "2") (pinfunction "2_2") (pintype "passive"))
      (node (ref "C24") (pin "2") (pinfunction "2_2") (pintype "passive"))
      (node (ref "IC3") (pin "2") (pinfunction "VCC_2") (pintype "power_in"))
      (node (ref "L7") (pin "2") (pinfunction "2_2") (pintype "passive"))
    )
    (net (code "33") (name "Net-(IC5-RF_IN)") (class "Default")
      (node (ref "C55") (pin "2") (pinfunction "2_2") (pintype "passive"))
      (node (ref "IC5") (pin "1") (pinfunction "RF_IN_1") (pintype "input"))
      (node (ref "R178") (pin "1") (pinfunction "1_1") (pintype "passive"))
    )
    (net (code "34") (name "Net-(IC5-RF_OUT)") (class "Default")
      (node (ref "C29") (pin "1") (pinfunction "1_1") (pintype "passive"))
      (node (ref "IC5") (pin "3") (pinfunction "RF_OUT_3") (pintype "output"))
      (node (ref "L1") (pin "3") (pinfunction "3_3") (pintype "passive"))
      (node (ref "R178") (pin "2") (pinfunction "2_2") (pintype "passive"))
    )
    (net (code "35") (name "Net-(IC17-IN)") (class "Default")
      (node (ref "C55") (pin "1") (pinfunction "1_1") (pintype "passive"))
      (node (ref "IC17") (pin "1") (pinfunction "IN_1") (pintype "bidirectional"))
    )
    (net (code "36") (name "Net-(IC17-OUT)") (class "Default")
      (node (ref "C36") (pin "2") (pinfunction "2_2") (pintype "passive"))
      (node (ref "IC17") (pin "2") (pinfunction "OUT_2") (pintype "bidirectional"))
    )
    (net (code "37") (name "Net-(IC23-EN)") (class "Default")
      (node (ref "IC23") (pin "5") (pinfunction "EN_5") (pintype "input"))
      (node (ref "R138") (pin "2") (pinfunction "2_2") (pintype "passive"))
    )
    (net (code "38") (name "Net-(IC23-RF1)") (class "Default")
      (node (ref "C49") (pin "1") (pinfunction "1_1") (pintype "passive"))
      (node (ref "IC23") (pin "9") (pinfunction "RF1_9") (pintype "bidirectional"))
    )
    (net (code "39") (name "Net-(IC23-RF2)") (class "Default")
      (node (ref "C47") (pin "1") (pinfunction "1_1") (pintype "passive"))
      (node (ref "IC23") (pin "12") (pinfunction "RF2_12") (pintype "bidirectional"))
    )
    (net (code "40") (name "Net-(IC23-RFC)") (class "Default")
      (node (ref "C29") (pin "2") (pinfunction "2_2") (pintype "passive"))
      (node (ref "IC23") (pin "3") (pinfunction "RFC_3") (pintype "bidirectional"))
    )
    (net (code "41") (name "Net-(IC23-VDD)") (class "Default")
      (node (ref "C38") (pin "1") (pinfunction "1_1") (pintype "passive"))
      (node (ref "C39") (pin "2") (pinfunction "2_2") (pintype "passive"))
      (node (ref "C40") (pin "2") (pinfunction "2_2") (pintype "passive"))
      (node (ref "IC23") (pin "1") (pinfunction "VDD_1") (pintype "power_in"))
      (node (ref "L6") (pin "1") (pinfunction "1_1") (pintype "passive"))
    )
    (net (code "42") (name "Net-(L1-Pad1)") (class "Default")
      (node (ref "L1") (pin "1") (pinfunction "1_1") (pintype "passive"))
      (node (ref "R137") (pin "2") (pinfunction "2_2") (pintype "passive"))
    )
    (net (code "43") (name "P5V0A") (class "Default")
      (node (ref "L6") (pin "2") (pinfunction "2_2") (pintype "passive"))
      (node (ref "L7") (pin "1") (pinfunction "1_1") (pintype "passive"))
    )
    (net (code "44") (name "P7V0A") (class "Default")
      (node (ref "C12") (pin "2") (pinfunction "2_2") (pintype "passive"))
      (node (ref "C27") (pin "2") (pinfunction "2_2") (pintype "passive"))
      (node (ref "R137") (pin "1") (pinfunction "1_1") (pintype "passive"))
    )
    (net (code "45") (name "unconnected-(IC23-NC-Pad4)") (class "Default")
      (node (ref "IC23") (pin "4") (pinfunction "NC_4") (pintype "passive+no_connect"))
    )
    (net (code "46") (name "unconnected-(IC23-NC-Pad6)") (class "Default")
      (node (ref "IC23") (pin "6") (pinfunction "NC_6") (pintype "passive+no_connect"))
    )
    (net (code "47") (name "unconnected-(IC23-NC-Pad7)") (class "Default")
      (node (ref "IC23") (pin "7") (pinfunction "NC_7") (pintype "passive+no_connect"))
    )
    (net (code "48") (name "unconnected-(IC23-NC-Pad8)") (class "Default")
      (node (ref "IC23") (pin "8") (pinfunction "NC_8") (pintype "passive+no_connect"))
    )
    (net (code "49") (name "unconnected-(IC23-NC-Pad13)") (class "Default")
      (node (ref "IC23") (pin "13") (pinfunction "NC_13") (pintype "passive+no_connect"))
    )
    (net (code "50") (name "unconnected-(IC23-NC-Pad14)") (class "Default")
      (node (ref "IC23") (pin "14") (pinfunction "NC_14") (pintype "passive+no_connect"))
    )
    (net (code "51") (name "unconnected-(IC23-NC-Pad15)") (class "Default")
      (node (ref "IC23") (pin "15") (pinfunction "NC_15") (pintype "passive+no_connect"))
    )
    (net (code "52") (name "unconnected-(IC23-NC-Pad16)") (class "Default")
      (node (ref "IC23") (pin "16") (pinfunction "NC_16") (pintype "passive+no_connect"))
    )
  )
)
